# Boost_Converter_Circuit.net
KiCad netlist of a schematic drawn in Altium Designer
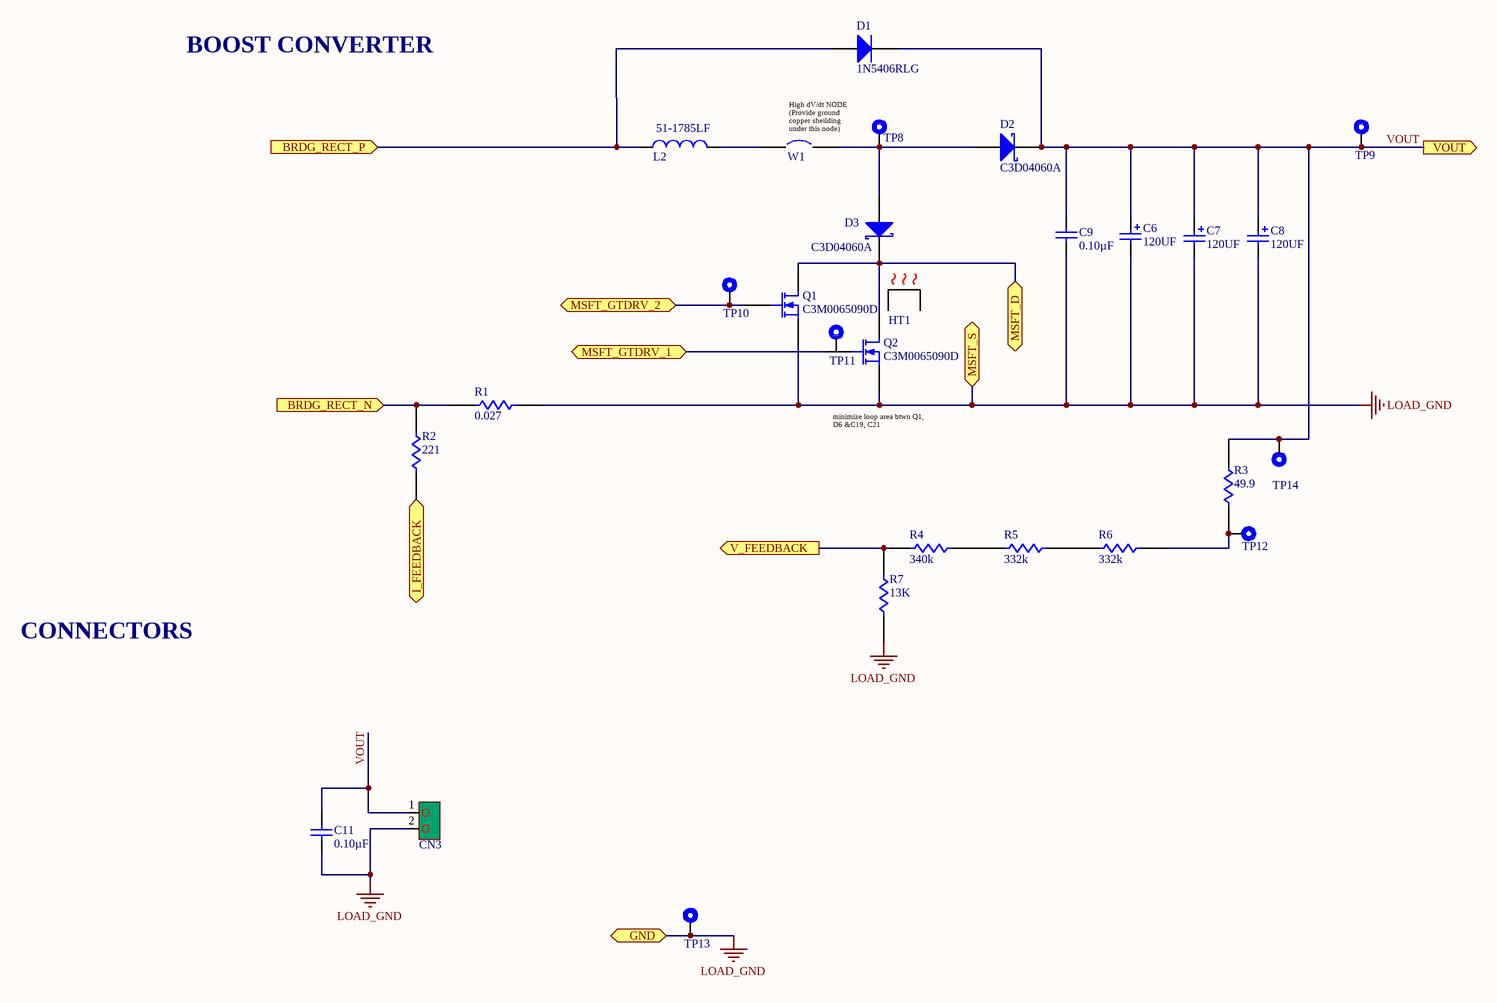
[diagram p0: Boost Converter Circuit.SchDoc]

(export (version "E")
  (design (tool "Eeschema 10.0.6"))
  (components
    (comp (ref "C6")
      (value "450QXW120MEFC18X31.5")
      (footprint "450QXW120MEFC18X31.5")
      (fields (field (name "CAPACITANCE") "120UF"))
      (libsource (lib "ucc28180") (part "450QXW120MEFC18X31.5"))
    )
    (comp (ref "C7")
      (value "450QXW120MEFC18X31.5")
      (footprint "450QXW120MEFC18X31.5")
      (fields (field (name "CAPACITANCE") "120UF"))
      (libsource (lib "ucc28180") (part "450QXW120MEFC18X31.5"))
    )
    (comp (ref "C8")
      (value "450QXW120MEFC18X31.5")
      (footprint "450QXW120MEFC18X31.5")
      (fields (field (name "CAPACITANCE") "120UF"))
      (libsource (lib "ucc28180") (part "450QXW120MEFC18X31.5"))
    )
    (comp (ref "C9")
      (value "GRM43DR72J104KW01L")
      (footprint "CAP1812")
      (description "CAP CER 0.1UF 630V X7R 1812")
      (fields (field (name "TOLERANCE") "±10%") (field (name "CAPACITANCE") "0.10µF"))
      (libsource (lib "ucc28180") (part "GRM43DR72J104KW01L"))
    )
    (comp (ref "C11")
      (value "GRM43DR72J104KW01L")
      (footprint "CAP1812")
      (description "CAP CER 0.1UF 630V X7R 1812")
      (fields (field (name "TOLERANCE") "±10%") (field (name "CAPACITANCE") "0.10µF"))
      (libsource (lib "ucc28180") (part "GRM43DR72J104KW01L"))
    )
    (comp (ref "CN3")
      (value "1935776")
      (footprint "CONN_1935776")
      (description "CONN TERM BLOCK 2POS 5.0MM")
      (fields (field (name "VOLTAGE") "300V"))
      (libsource (lib "ucc28180") (part "1935776"))
    )
    (comp (ref "D1")
      (value "1N5406RLG")
      (footprint "1N5406-DO201AD")
      (description "DIODE GEN PURP 600V 3A DO201AD")
      (fields
        (field (name "MANUFACTURER") "ON Semiconductor")
        (field (name "MANUFACTURER PART NUMBER") "1N5406RLG")
      )
      (libsource (lib "ucc28180-V03") (part "1N5406RLG"))
    )
    (comp (ref "D2")
      (value "C3D04060A")
      (footprint "C3D04060A")
      (description "DIODE SCHOTTKY 600V 4A TO220-2")
      (fields (field (name "MANUFACTURER PART NUMBER 1") "C3D04060A"))
      (libsource (lib "ucc28180") (part "C3D04060A"))
    )
    (comp (ref "D3")
      (value "C3D04060A")
      (footprint "C3D04060A")
      (description "DIODE SCHOTTKY 600V 4A TO220-2")
      (fields (field (name "MANUFACTURER PART NUMBER 1") "C3D04060A"))
      (libsource (lib "ucc28180-V04") (part "C3D04060A"))
    )
    (comp (ref "HT1")
      (value "HT_78245")
      (footprint "HT-78245")
      (libsource (lib "ucc28180-V04") (part "HT_78245"))
    )
    (comp (ref "L2")
      (value "51-1785LF")
      (footprint "G-51-185LF")
      (fields (field (name "MANUFACTURER") "Gowanda Electronics"))
      (libsource (lib "ucc28180-V02") (part "51-1785LF"))
    )
    (comp (ref "Q1")
      (value "C3M0065090D")
      (footprint "TO-247-3")
      (description "MOSFET N-CH 900V 36A TO247-3")
      (fields (field (name "MANUFACTURER PART NUMBER 1") "C3M0065090D"))
      (libsource (lib "ucc28180-V04") (part "C3M0065090D"))
    )
    (comp (ref "Q2")
      (value "C3M0065090D")
      (footprint "TO-247-3")
      (description "MOSFET N-CH 900V 36A TO247-3")
      (fields (field (name "MANUFACTURER PART NUMBER 1") "C3M0065090D"))
      (libsource (lib "ucc28180-V04") (part "C3M0065090D"))
    )
    (comp (ref "R1")
      (value "CRCW2512R0.027")
      (footprint "RES2512")
      (fields (field (name "RESISTANCE") "0.027"))
      (libsource (lib "ucc28180") (part "CRCW2512R0.027"))
    )
    (comp (ref "R2")
      (value "RC0805FR-07221RL")
      (footprint "RES0805_New")
      (description "RES SMD 221 OHM 1% 1/8W 0805")
      (fields
        (field (name "MANUFACTURER") "Yageo")
        (field (name "TOLERANCE") "±1%")
        (field (name "RESISTANCE") "221")
      )
      (libsource (lib "ucc28180-V04") (part "RC0805FR-07221RL"))
    )
    (comp (ref "R3")
      (value "CRCW120649R9FKEA")
      (footprint "RES1206")
      (description "RES SMD 49.9 OHM 1% 1/4W 1206")
      (fields (field (name "TOLERANCE") "±1%") (field (name "RESISTANCE (OHMS)") "49.9"))
      (libsource (lib "ucc28180") (part "CRCW120649R9FKEA"))
    )
    (comp (ref "R4")
      (value "CRCW0805340KFKEA")
      (footprint "RES0805_New")
      (description "RES SMD 340K OHM 1% 1/8W 0805")
      (fields (field (name "TOLERANCE") "±1%") (field (name "RESISTANCE (OHMS)") "340k"))
      (libsource (lib "ucc28180") (part "CRCW0805340KFKEA"))
    )
    (comp (ref "R5")
      (value "CRCW0805332KFKEA")
      (footprint "RES0805_New")
      (description "RES SMD 332K OHM 1% 1/8W 0805")
      (fields (field (name "TOLERANCE") "±1%") (field (name "RESISTANCE (OHMS)") "332k"))
      (libsource (lib "ucc28180") (part "CRCW0805332KFKEA"))
    )
    (comp (ref "R6")
      (value "CRCW0805332KFKEA")
      (footprint "RES0805_New")
      (description "RES SMD 332K OHM 1% 1/8W 0805")
      (fields (field (name "TOLERANCE") "±1%") (field (name "RESISTANCE (OHMS)") "332k"))
      (libsource (lib "ucc28180") (part "CRCW0805332KFKEA"))
    )
    (comp (ref "R7")
      (value "RC0805FR-0713KL")
      (footprint "RES0805_New")
      (description "RES SMD 13K OHM 1% 1/8W 0805")
      (fields
        (field (name "MANUFACTURER") "Yageo")
        (field (name "TOLERANCE") "±1%")
        (field (name "RESISTANCE") "13K")
      )
      (libsource (lib "ucc28180-V04") (part "RC0805FR-0713KL"))
    )
    (comp (ref "TP8")
      (value "5006")
      (footprint "Test Point")
      (description "TEST POINT PC COMPACT .063\"D BLK")
      (libsource (lib "ucc28180") (part "5006"))
    )
    (comp (ref "TP9")
      (value "5006")
      (footprint "Test Point")
      (description "TEST POINT PC COMPACT .063\"D BLK")
      (libsource (lib "ucc28180") (part "5006"))
    )
    (comp (ref "TP10")
      (value "5006")
      (footprint "Test Point")
      (description "TEST POINT PC COMPACT .063\"D BLK")
      (libsource (lib "ucc28180") (part "5006"))
    )
    (comp (ref "TP11")
      (value "5006")
      (footprint "Test Point")
      (description "TEST POINT PC COMPACT .063\"D BLK")
      (libsource (lib "ucc28180-V04") (part "5006"))
    )
    (comp (ref "TP12")
      (value "5006")
      (footprint "Test Point")
      (description "TEST POINT PC COMPACT .063\"D BLK")
      (libsource (lib "ucc28180") (part "5006"))
    )
    (comp (ref "TP13")
      (value "5006")
      (footprint "Test Point")
      (description "TEST POINT PC COMPACT .063\"D BLK")
      (libsource (lib "ucc28180") (part "5006"))
    )
    (comp (ref "TP14")
      (value "5006")
      (footprint "Test Point")
      (description "TEST POINT PC COMPACT .063\"D BLK")
      (libsource (lib "ucc28180-V04") (part "5006"))
    )
    (comp (ref "W1")
      (value "Wire")
      (footprint "Current Sense Wire")
      (libsource (lib "ucc28180-V02") (part "Wire"))
    )
  )
  (nets
    (net (code "1") (name "/BRDG_RECT_N") (class "Default")
      (node (ref "R1") (pin "2") (pinfunction "2_2") (pintype "passive"))
      (node (ref "R2") (pin "1") (pinfunction "1_1") (pintype "passive"))
    )
    (net (code "2") (name "/BRDG_RECT_P") (class "Default")
      (node (ref "D1") (pin "2") (pinfunction "A_2") (pintype "passive"))
      (node (ref "L2") (pin "1") (pinfunction "1_1") (pintype "passive"))
    )
    (net (code "3") (name "/I_FEEDBACK") (class "Default")
      (node (ref "R2") (pin "2") (pinfunction "2_2") (pintype "passive"))
    )
    (net (code "4") (name "/MSFT_D") (class "Default")
      (node (ref "D3") (pin "1") (pinfunction "K_1") (pintype "passive"))
      (node (ref "Q1") (pin "2") (pinfunction "D_2") (pintype "passive"))
      (node (ref "Q2") (pin "2") (pinfunction "D_2") (pintype "passive"))
    )
    (net (code "5") (name "/MSFT_GTDRV_1") (class "Default")
      (node (ref "Q2") (pin "1") (pinfunction "G_1") (pintype "passive"))
    )
    (net (code "6") (name "/MSFT_GTDRV_2") (class "Default")
      (node (ref "Q1") (pin "1") (pinfunction "G_1") (pintype "passive"))
      (node (ref "TP10") (pin "1") (pinfunction "1_1") (pintype "passive"))
    )
    (net (code "7") (name "/VOUT") (class "Default")
      (node (ref "C11") (pin "2") (pinfunction "2_2") (pintype "passive"))
      (node (ref "C6") (pin "1") (pinfunction "1_1") (pintype "passive"))
      (node (ref "C7") (pin "1") (pinfunction "1_1") (pintype "passive"))
      (node (ref "C8") (pin "1") (pinfunction "1_1") (pintype "passive"))
      (node (ref "C9") (pin "2") (pinfunction "2_2") (pintype "passive"))
      (node (ref "CN3") (pin "1") (pintype "passive"))
      (node (ref "D1") (pin "1") (pinfunction "K_1") (pintype "passive"))
      (node (ref "D2") (pin "1") (pinfunction "K_1") (pintype "passive"))
      (node (ref "R3") (pin "1") (pinfunction "1_1") (pintype "passive"))
      (node (ref "TP14") (pin "1") (pinfunction "1_1") (pintype "passive"))
      (node (ref "TP9") (pin "1") (pinfunction "1_1") (pintype "passive"))
    )
    (net (code "8") (name "/V_FEEDBACK") (class "Default")
      (node (ref "R4") (pin "2") (pinfunction "2_2") (pintype "passive"))
      (node (ref "R7") (pin "1") (pinfunction "1_1") (pintype "passive"))
    )
    (net (code "9") (name "LOAD_GND") (class "Default")
      (node (ref "C11") (pin "1") (pinfunction "1_1") (pintype "passive"))
      (node (ref "C6") (pin "2") (pinfunction "2_2") (pintype "passive"))
      (node (ref "C7") (pin "2") (pinfunction "2_2") (pintype "passive"))
      (node (ref "C8") (pin "2") (pinfunction "2_2") (pintype "passive"))
      (node (ref "C9") (pin "1") (pinfunction "1_1") (pintype "passive"))
      (node (ref "CN3") (pin "2") (pintype "passive"))
      (node (ref "Q1") (pin "3") (pinfunction "S_3") (pintype "passive"))
      (node (ref "Q2") (pin "3") (pinfunction "S_3") (pintype "passive"))
      (node (ref "R1") (pin "1") (pinfunction "1_1") (pintype "passive"))
      (node (ref "R7") (pin "2") (pinfunction "2_2") (pintype "passive"))
      (node (ref "TP13") (pin "1") (pinfunction "1_1") (pintype "passive"))
    )
    (net (code "10") (name "Net-(D2-A)") (class "Default")
      (node (ref "D2") (pin "2") (pinfunction "A_2") (pintype "passive"))
      (node (ref "D3") (pin "2") (pinfunction "A_2") (pintype "passive"))
      (node (ref "TP8") (pin "1") (pinfunction "1_1") (pintype "passive"))
      (node (ref "W1") (pin "2") (pinfunction "2_2") (pintype "passive"))
    )
    (net (code "11") (name "Net-(L2-Pad2)") (class "Default")
      (node (ref "L2") (pin "2") (pinfunction "2_2") (pintype "passive"))
      (node (ref "W1") (pin "1") (pinfunction "1_1") (pintype "passive"))
    )
    (net (code "12") (name "Net-(R3-Pad2)") (class "Default")
      (node (ref "R3") (pin "2") (pinfunction "2_2") (pintype "passive"))
      (node (ref "R6") (pin "1") (pinfunction "1_1") (pintype "passive"))
      (node (ref "TP12") (pin "1") (pinfunction "1_1") (pintype "passive"))
    )
    (net (code "13") (name "Net-(R4-Pad1)") (class "Default")
      (node (ref "R4") (pin "1") (pinfunction "1_1") (pintype "passive"))
      (node (ref "R5") (pin "2") (pinfunction "2_2") (pintype "passive"))
    )
    (net (code "14") (name "Net-(R5-Pad1)") (class "Default")
      (node (ref "R5") (pin "1") (pinfunction "1_1") (pintype "passive"))
      (node (ref "R6") (pin "2") (pinfunction "2_2") (pintype "passive"))
    )
    (net (code "15") (name "unconnected-(TP11-Pad1)") (class "Default")
      (node (ref "TP11") (pin "1") (pinfunction "1_1") (pintype "passive"))
    )
  )
)
